# RL.net
KiCad netlist of a schematic drawn in EAGLE
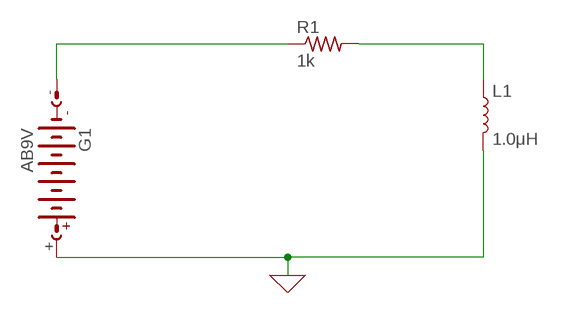
[diagram p0: schematic, sheet 1]

(export (version "E")
  (design (tool "Eeschema 10.0.6"))
  (components
    (comp (ref "G1")
      (value "AB9V")
      (footprint "eagle-import:AB9V")
      (libsource (lib "eagle-import") (part "AB9V"))
    )
    (comp (ref "L1")
      (value "1.0μH")
      (footprint "eagle-import:0805-WIDE")
      (libsource (lib "eagle-import") (part "1.0μH-0805_WIDE-1.0μH-1.4A-0.07OHM-1.4MM_H"))
    )
    (comp (ref "R1")
      (value "1k")
      (footprint "eagle-import:0204V")
      (libsource (lib "eagle-import") (part "R-US_0204/2V"))
    )
  )
  (nets
    (net (code "1") (name "GND") (class "Default")
      (node (ref "G1") (pin "+") (pinfunction "+_+") (pintype "passive"))
      (node (ref "L1") (pin "2") (pinfunction "2_2") (pintype "passive"))
    )
    (net (code "2") (name "Net-(G1-Pad-)") (class "Default")
      (node (ref "G1") (pin "-") (pinfunction "-_-") (pintype "passive"))
      (node (ref "R1") (pin "1") (pinfunction "1_1") (pintype "passive"))
    )
    (net (code "3") (name "Net-(L1-Pad1)") (class "Default")
      (node (ref "L1") (pin "1") (pinfunction "1_1") (pintype "passive"))
      (node (ref "R1") (pin "2") (pinfunction "2_2") (pintype "passive"))
    )
  )
)
